# LCD_-_Copy.net
KiCad netlist of a schematic drawn in Altium Designer
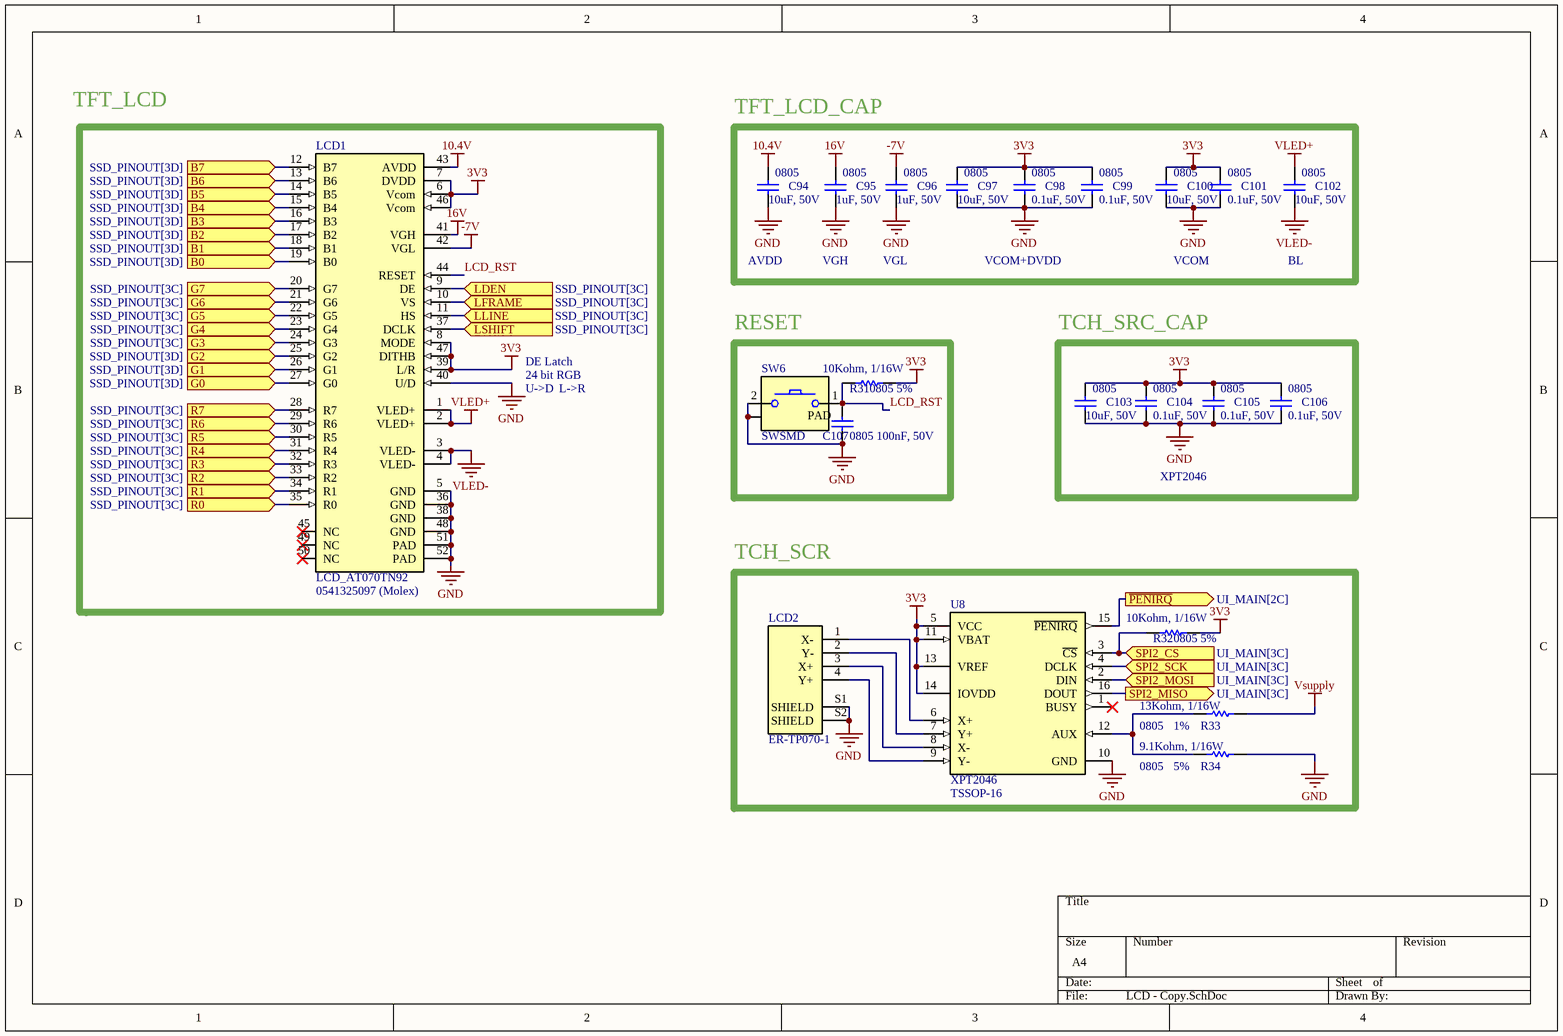
[diagram p0: LCD - Copy.SchDoc]

(export (version "E")
  (design (tool "Eeschema 10.0.6"))
  (components
    (comp (ref "C94")
      (value "10uF, 50V")
      (footprint "C_0805")
      (description "CAP_0805")
      (fields (field (name "PACKAGE") "0805"))
      (libsource (lib "DisplayLib") (part "CAP_0805"))
    )
    (comp (ref "C95")
      (value "1uF, 50V")
      (footprint "C_0805")
      (description "CAP_0805")
      (fields (field (name "PACKAGE") "0805"))
      (libsource (lib "DisplayLib") (part "CAP_0805"))
    )
    (comp (ref "C96")
      (value "1uF, 50V")
      (footprint "C_0805")
      (description "CAP_0805")
      (fields (field (name "PACKAGE") "0805"))
      (libsource (lib "DisplayLib") (part "CAP_0805"))
    )
    (comp (ref "C97")
      (value "10uF, 50V")
      (footprint "C_0805")
      (description "CAP_0805")
      (fields (field (name "PACKAGE") "0805"))
      (libsource (lib "DisplayLib") (part "CAP_0805"))
    )
    (comp (ref "C98")
      (value "0.1uF, 50V")
      (footprint "C_0805")
      (description "CAP_0805")
      (fields (field (name "PACKAGE") "0805"))
      (libsource (lib "DisplayLib") (part "CAP_0805"))
    )
    (comp (ref "C99")
      (value "0.1uF, 50V")
      (footprint "C_0805")
      (description "CAP_0805")
      (fields (field (name "PACKAGE") "0805"))
      (libsource (lib "DisplayLib") (part "CAP_0805"))
    )
    (comp (ref "C100")
      (value "10uF, 50V")
      (footprint "C_0805")
      (description "CAP_0805")
      (fields (field (name "PACKAGE") "0805"))
      (libsource (lib "DisplayLib") (part "CAP_0805"))
    )
    (comp (ref "C101")
      (value "0.1uF, 50V")
      (footprint "C_0805")
      (description "CAP_0805")
      (fields (field (name "PACKAGE") "0805"))
      (libsource (lib "DisplayLib") (part "CAP_0805"))
    )
    (comp (ref "C102")
      (value "10uF, 50V")
      (footprint "C_0805")
      (description "CAP_0805")
      (fields (field (name "PACKAGE") "0805"))
      (libsource (lib "DisplayLib") (part "CAP_0805"))
    )
    (comp (ref "C103")
      (value "10uF, 50V")
      (footprint "C_0805")
      (description "CAP_0805")
      (fields (field (name "PACKAGE") "0805"))
      (libsource (lib "DisplayLib") (part "CAP_0805"))
    )
    (comp (ref "C104")
      (value "0.1uF, 50V")
      (footprint "C_0805")
      (description "CAP_0805")
      (fields (field (name "PACKAGE") "0805"))
      (libsource (lib "DisplayLib") (part "CAP_0805"))
    )
    (comp (ref "C105")
      (value "0.1uF, 50V")
      (footprint "C_0805")
      (description "CAP_0805")
      (fields (field (name "PACKAGE") "0805"))
      (libsource (lib "DisplayLib") (part "CAP_0805"))
    )
    (comp (ref "C106")
      (value "0.1uF, 50V")
      (footprint "C_0805")
      (description "CAP_0805")
      (fields (field (name "PACKAGE") "0805"))
      (libsource (lib "DisplayLib") (part "CAP_0805"))
    )
    (comp (ref "C107")
      (value "100nF, 50V")
      (footprint "C_0805")
      (description "CAP_0805")
      (fields (field (name "PACKAGE") "0805"))
      (libsource (lib "DisplayLib") (part "CAP_0805"))
    )
    (comp (ref "LCD1")
      (value "LCD_AT070TN92")
      (footprint "CONN_LCD_AT070TN90")
      (description "LCD 7 inch (800 x 3(RGB) x 480) RES\r\n__NOTE THAT THIS IS FFC 50PINS CONN w/ THE LCD FOOTPRINT!__")
      (fields (field (name "CONNECTOR PART NUMBER") "0541325097 (Molex)"))
      (libsource (lib "DisplayLib") (part "LCD_AT070TN92"))
    )
    (comp (ref "LCD2")
      (value "ER-TP070-1")
      (footprint "ER-TP070-1")
      (description "7 ”Resistive Touch Panel")
      (libsource (lib "DisplayLib") (part "ER-TP070-1"))
    )
    (comp (ref "R31")
      (value "10Kohm, 1/16W")
      (footprint "R_0805")
      (description "RES_0805")
      (fields (field (name "PACKAGE") "0805") (field (name "ACC") "5%"))
      (libsource (lib "DisplayLib") (part "RES_0805"))
    )
    (comp (ref "R32")
      (value "10Kohm, 1/16W")
      (footprint "R_0805")
      (description "RES_0805")
      (fields (field (name "PACKAGE") "0805") (field (name "ACC") "5%"))
      (libsource (lib "DisplayLib") (part "RES_0805"))
    )
    (comp (ref "R33")
      (value "13Kohm, 1/16W")
      (footprint "R_0805")
      (description "RES_0805")
      (fields (field (name "PACKAGE") "0805") (field (name "ACC") "1%"))
      (libsource (lib "DisplayLib") (part "RES_0805"))
    )
    (comp (ref "R34")
      (value "9.1Kohm, 1/16W")
      (footprint "R_0805")
      (description "RES_0805")
      (fields (field (name "PACKAGE") "0805") (field (name "ACC") "5%"))
      (libsource (lib "DisplayLib") (part "RES_0805"))
    )
    (comp (ref "SW6")
      (value "SWSMD")
      (footprint "SW_SMD")
      (description "SW_SMD")
      (libsource (lib "DisplayLib") (part "SWSMD"))
    )
    (comp (ref "U8")
      (value "XPT2046")
      (footprint "PKG_TSSOP-16")
      (fields (field (name "PACKAGE") "TSSOP-16"))
      (libsource (lib "DisplayLib") (part "XPT2046"))
    )
  )
  (nets
    (net (code "1") (name "-7V") (class "Default")
      (node (ref "C96") (pin "2") (pinfunction "2_2") (pintype "passive"))
      (node (ref "LCD1") (pin "42") (pinfunction "VGL_42") (pintype "power_in"))
    )
    (net (code "2") (name "/B0") (class "Default")
      (node (ref "LCD1") (pin "19") (pinfunction "B0_19") (pintype "input"))
    )
    (net (code "3") (name "/B1") (class "Default")
      (node (ref "LCD1") (pin "18") (pinfunction "B1_18") (pintype "input"))
    )
    (net (code "4") (name "/B2") (class "Default")
      (node (ref "LCD1") (pin "17") (pinfunction "B2_17") (pintype "input"))
    )
    (net (code "5") (name "/B3") (class "Default")
      (node (ref "LCD1") (pin "16") (pinfunction "B3_16") (pintype "input"))
    )
    (net (code "6") (name "/B4") (class "Default")
      (node (ref "LCD1") (pin "15") (pinfunction "B4_15") (pintype "input"))
    )
    (net (code "7") (name "/B5") (class "Default")
      (node (ref "LCD1") (pin "14") (pinfunction "B5_14") (pintype "input"))
    )
    (net (code "8") (name "/B6") (class "Default")
      (node (ref "LCD1") (pin "13") (pinfunction "B6_13") (pintype "input"))
    )
    (net (code "9") (name "/B7") (class "Default")
      (node (ref "LCD1") (pin "12") (pinfunction "B7_12") (pintype "input"))
    )
    (net (code "10") (name "/G0") (class "Default")
      (node (ref "LCD1") (pin "27") (pinfunction "G0_27") (pintype "input"))
    )
    (net (code "11") (name "/G1") (class "Default")
      (node (ref "LCD1") (pin "26") (pinfunction "G1_26") (pintype "input"))
    )
    (net (code "12") (name "/G2") (class "Default")
      (node (ref "LCD1") (pin "25") (pinfunction "G2_25") (pintype "input"))
    )
    (net (code "13") (name "/G3") (class "Default")
      (node (ref "LCD1") (pin "24") (pinfunction "G3_24") (pintype "input"))
    )
    (net (code "14") (name "/G4") (class "Default")
      (node (ref "LCD1") (pin "23") (pinfunction "G4_23") (pintype "input"))
    )
    (net (code "15") (name "/G5") (class "Default")
      (node (ref "LCD1") (pin "22") (pinfunction "G5_22") (pintype "input"))
    )
    (net (code "16") (name "/G6") (class "Default")
      (node (ref "LCD1") (pin "21") (pinfunction "G6_21") (pintype "input"))
    )
    (net (code "17") (name "/G7") (class "Default")
      (node (ref "LCD1") (pin "20") (pinfunction "G7_20") (pintype "input"))
    )
    (net (code "18") (name "/LCD_RST") (class "Default")
      (node (ref "C107") (pin "2") (pinfunction "2_2") (pintype "passive"))
      (node (ref "LCD1") (pin "44") (pinfunction "RESET_44") (pintype "input"))
      (node (ref "R31") (pin "2") (pinfunction "2_2") (pintype "passive"))
      (node (ref "SW6") (pin "1") (pinfunction "1_1") (pintype "passive"))
    )
    (net (code "19") (name "/LDEN") (class "Default")
      (node (ref "LCD1") (pin "9") (pinfunction "DE_9") (pintype "input"))
    )
    (net (code "20") (name "/LFRAME") (class "Default")
      (node (ref "LCD1") (pin "10") (pinfunction "VS_10") (pintype "input"))
    )
    (net (code "21") (name "/LLINE") (class "Default")
      (node (ref "LCD1") (pin "11") (pinfunction "HS_11") (pintype "input"))
    )
    (net (code "22") (name "/LSHIFT") (class "Default")
      (node (ref "LCD1") (pin "37") (pinfunction "DCLK_37") (pintype "input"))
    )
    (net (code "23") (name "/R0") (class "Default")
      (node (ref "LCD1") (pin "35") (pinfunction "R0_35") (pintype "input"))
    )
    (net (code "24") (name "/R1") (class "Default")
      (node (ref "LCD1") (pin "34") (pinfunction "R1_34") (pintype "input"))
    )
    (net (code "25") (name "/R2") (class "Default")
      (node (ref "LCD1") (pin "33") (pinfunction "R2_33") (pintype "input"))
    )
    (net (code "26") (name "/R3") (class "Default")
      (node (ref "LCD1") (pin "32") (pinfunction "R3_32") (pintype "input"))
    )
    (net (code "27") (name "/R4") (class "Default")
      (node (ref "LCD1") (pin "31") (pinfunction "R4_31") (pintype "input"))
    )
    (net (code "28") (name "/R5") (class "Default")
      (node (ref "LCD1") (pin "30") (pinfunction "R5_30") (pintype "input"))
    )
    (net (code "29") (name "/R6") (class "Default")
      (node (ref "LCD1") (pin "29") (pinfunction "R6_29") (pintype "input"))
    )
    (net (code "30") (name "/R7") (class "Default")
      (node (ref "LCD1") (pin "28") (pinfunction "R7_28") (pintype "input"))
    )
    (net (code "31") (name "/SPI2_CS") (class "Default")
      (node (ref "R32") (pin "2") (pinfunction "2_2") (pintype "passive"))
      (node (ref "U8") (pin "3") (pinfunction "~{CS}_3") (pintype "input"))
    )
    (net (code "32") (name "/SPI2_MISO") (class "Default")
      (node (ref "U8") (pin "16") (pinfunction "DOUT_16") (pintype "output"))
    )
    (net (code "33") (name "/SPI2_MOSI") (class "Default")
      (node (ref "U8") (pin "2") (pinfunction "DIN_2") (pintype "input"))
    )
    (net (code "34") (name "/SPI2_SCK") (class "Default")
      (node (ref "U8") (pin "4") (pinfunction "DCLK_4") (pintype "input"))
    )
    (net (code "35") (name "/~{PENIRQ}") (class "Default")
      (node (ref "U8") (pin "15") (pinfunction "~{PENIRQ}_15") (pintype "output"))
    )
    (net (code "36") (name "3V3") (class "Default")
      (node (ref "C100") (pin "2") (pinfunction "2_2") (pintype "passive"))
      (node (ref "C101") (pin "2") (pinfunction "2_2") (pintype "passive"))
      (node (ref "C103") (pin "2") (pinfunction "2_2") (pintype "passive"))
      (node (ref "C104") (pin "2") (pinfunction "2_2") (pintype "passive"))
      (node (ref "C105") (pin "2") (pinfunction "2_2") (pintype "passive"))
      (node (ref "C106") (pin "2") (pinfunction "2_2") (pintype "passive"))
      (node (ref "C97") (pin "2") (pinfunction "2_2") (pintype "passive"))
      (node (ref "C98") (pin "2") (pinfunction "2_2") (pintype "passive"))
      (node (ref "C99") (pin "2") (pinfunction "2_2") (pintype "passive"))
      (node (ref "LCD1") (pin "39") (pinfunction "L/R_39") (pintype "input"))
      (node (ref "LCD1") (pin "46") (pinfunction "Vcom_46") (pintype "input"))
      (node (ref "LCD1") (pin "47") (pinfunction "DITHB_47") (pintype "input"))
      (node (ref "LCD1") (pin "6") (pinfunction "Vcom_6") (pintype "input"))
      (node (ref "LCD1") (pin "7") (pinfunction "DVDD_7") (pintype "power_in"))
      (node (ref "LCD1") (pin "8") (pinfunction "MODE_8") (pintype "input"))
      (node (ref "R31") (pin "1") (pinfunction "1_1") (pintype "passive"))
      (node (ref "R32") (pin "1") (pinfunction "1_1") (pintype "passive"))
      (node (ref "U8") (pin "11") (pinfunction "VBAT_11") (pintype "input"))
      (node (ref "U8") (pin "13") (pinfunction "VREF_13") (pintype "power_in"))
      (node (ref "U8") (pin "14") (pinfunction "IOVDD_14") (pintype "power_in"))
      (node (ref "U8") (pin "5") (pinfunction "VCC_5") (pintype "power_in"))
    )
    (net (code "37") (name "10.4V") (class "Default")
      (node (ref "C94") (pin "2") (pinfunction "2_2") (pintype "passive"))
      (node (ref "LCD1") (pin "43") (pinfunction "AVDD_43") (pintype "power_in"))
    )
    (net (code "38") (name "16V") (class "Default")
      (node (ref "C95") (pin "2") (pinfunction "2_2") (pintype "passive"))
      (node (ref "LCD1") (pin "41") (pinfunction "VGH_41") (pintype "power_in"))
    )
    (net (code "39") (name "GND") (class "Default")
      (node (ref "C100") (pin "1") (pinfunction "1_1") (pintype "passive"))
      (node (ref "C101") (pin "1") (pinfunction "1_1") (pintype "passive"))
      (node (ref "C103") (pin "1") (pinfunction "1_1") (pintype "passive"))
      (node (ref "C104") (pin "1") (pinfunction "1_1") (pintype "passive"))
      (node (ref "C105") (pin "1") (pinfunction "1_1") (pintype "passive"))
      (node (ref "C106") (pin "1") (pinfunction "1_1") (pintype "passive"))
      (node (ref "C107") (pin "1") (pinfunction "1_1") (pintype "passive"))
      (node (ref "C94") (pin "1") (pinfunction "1_1") (pintype "passive"))
      (node (ref "C95") (pin "1") (pinfunction "1_1") (pintype "passive"))
      (node (ref "C96") (pin "1") (pinfunction "1_1") (pintype "passive"))
      (node (ref "C97") (pin "1") (pinfunction "1_1") (pintype "passive"))
      (node (ref "C98") (pin "1") (pinfunction "1_1") (pintype "passive"))
      (node (ref "C99") (pin "1") (pinfunction "1_1") (pintype "passive"))
      (node (ref "LCD1") (pin "36") (pinfunction "GND_36") (pintype "power_in"))
      (node (ref "LCD1") (pin "38") (pinfunction "GND_38") (pintype "power_in"))
      (node (ref "LCD1") (pin "40") (pinfunction "U/D_40") (pintype "input"))
      (node (ref "LCD1") (pin "48") (pinfunction "GND_48") (pintype "power_in"))
      (node (ref "LCD1") (pin "5") (pinfunction "GND_5") (pintype "power_in"))
      (node (ref "LCD1") (pin "51") (pinfunction "PAD_51") (pintype "power_in"))
      (node (ref "LCD1") (pin "52") (pinfunction "PAD_52") (pintype "power_in"))
      (node (ref "LCD2") (pin "S1") (pinfunction "SHIELD_S1") (pintype "passive"))
      (node (ref "LCD2") (pin "S2") (pinfunction "SHIELD_S2") (pintype "passive"))
      (node (ref "R34") (pin "1") (pinfunction "1_1") (pintype "passive"))
      (node (ref "SW6") (pin "0") (pinfunction "PAD_0") (pintype "passive"))
      (node (ref "SW6") (pin "2") (pinfunction "2_2") (pintype "passive"))
      (node (ref "U8") (pin "10") (pinfunction "GND_10") (pintype "power_in"))
    )
    (net (code "40") (name "Net-(LCD2-X+)") (class "Default")
      (node (ref "LCD2") (pin "3") (pinfunction "X+_3") (pintype "passive"))
      (node (ref "U8") (pin "8") (pinfunction "X-_8") (pintype "input"))
    )
    (net (code "41") (name "Net-(LCD2-X-)") (class "Default")
      (node (ref "LCD2") (pin "1") (pinfunction "X-_1") (pintype "passive"))
      (node (ref "U8") (pin "6") (pinfunction "X+_6") (pintype "input"))
    )
    (net (code "42") (name "Net-(LCD2-Y+)") (class "Default")
      (node (ref "LCD2") (pin "4") (pinfunction "Y+_4") (pintype "passive"))
      (node (ref "U8") (pin "9") (pinfunction "Y-_9") (pintype "input"))
    )
    (net (code "43") (name "Net-(LCD2-Y-)") (class "Default")
      (node (ref "LCD2") (pin "2") (pinfunction "Y-_2") (pintype "passive"))
      (node (ref "U8") (pin "7") (pinfunction "Y+_7") (pintype "input"))
    )
    (net (code "44") (name "Net-(U8-AUX)") (class "Default")
      (node (ref "R33") (pin "2") (pinfunction "2_2") (pintype "passive"))
      (node (ref "R34") (pin "2") (pinfunction "2_2") (pintype "passive"))
      (node (ref "U8") (pin "12") (pinfunction "AUX_12") (pintype "input"))
    )
    (net (code "45") (name "VLED+") (class "Default")
      (node (ref "C102") (pin "2") (pinfunction "2_2") (pintype "passive"))
      (node (ref "LCD1") (pin "1") (pinfunction "VLED+_1") (pintype "power_in"))
      (node (ref "LCD1") (pin "2") (pinfunction "VLED+_2") (pintype "power_in"))
    )
    (net (code "46") (name "VLED-") (class "Default")
      (node (ref "C102") (pin "1") (pinfunction "1_1") (pintype "passive"))
      (node (ref "LCD1") (pin "3") (pinfunction "VLED-_3") (pintype "power_in"))
      (node (ref "LCD1") (pin "4") (pinfunction "VLED-_4") (pintype "power_in"))
    )
    (net (code "47") (name "Vsupply") (class "Default")
      (node (ref "R33") (pin "1") (pinfunction "1_1") (pintype "passive"))
    )
    (net (code "48") (name "unconnected-(LCD1-NC-Pad45)") (class "Default")
      (node (ref "LCD1") (pin "45") (pinfunction "NC_45") (pintype "passive+no_connect"))
    )
    (net (code "49") (name "unconnected-(LCD1-NC-Pad49)") (class "Default")
      (node (ref "LCD1") (pin "49") (pinfunction "NC_49") (pintype "passive+no_connect"))
    )
    (net (code "50") (name "unconnected-(LCD1-NC-Pad50)") (class "Default")
      (node (ref "LCD1") (pin "50") (pinfunction "NC_50") (pintype "passive+no_connect"))
    )
    (net (code "51") (name "unconnected-(U8-BUSY-Pad1)") (class "Default")
      (node (ref "U8") (pin "1") (pinfunction "BUSY_1") (pintype "output+no_connect"))
    )
  )
)
